# rev1_header_done.net
KiCad netlist of a schematic drawn in EAGLE
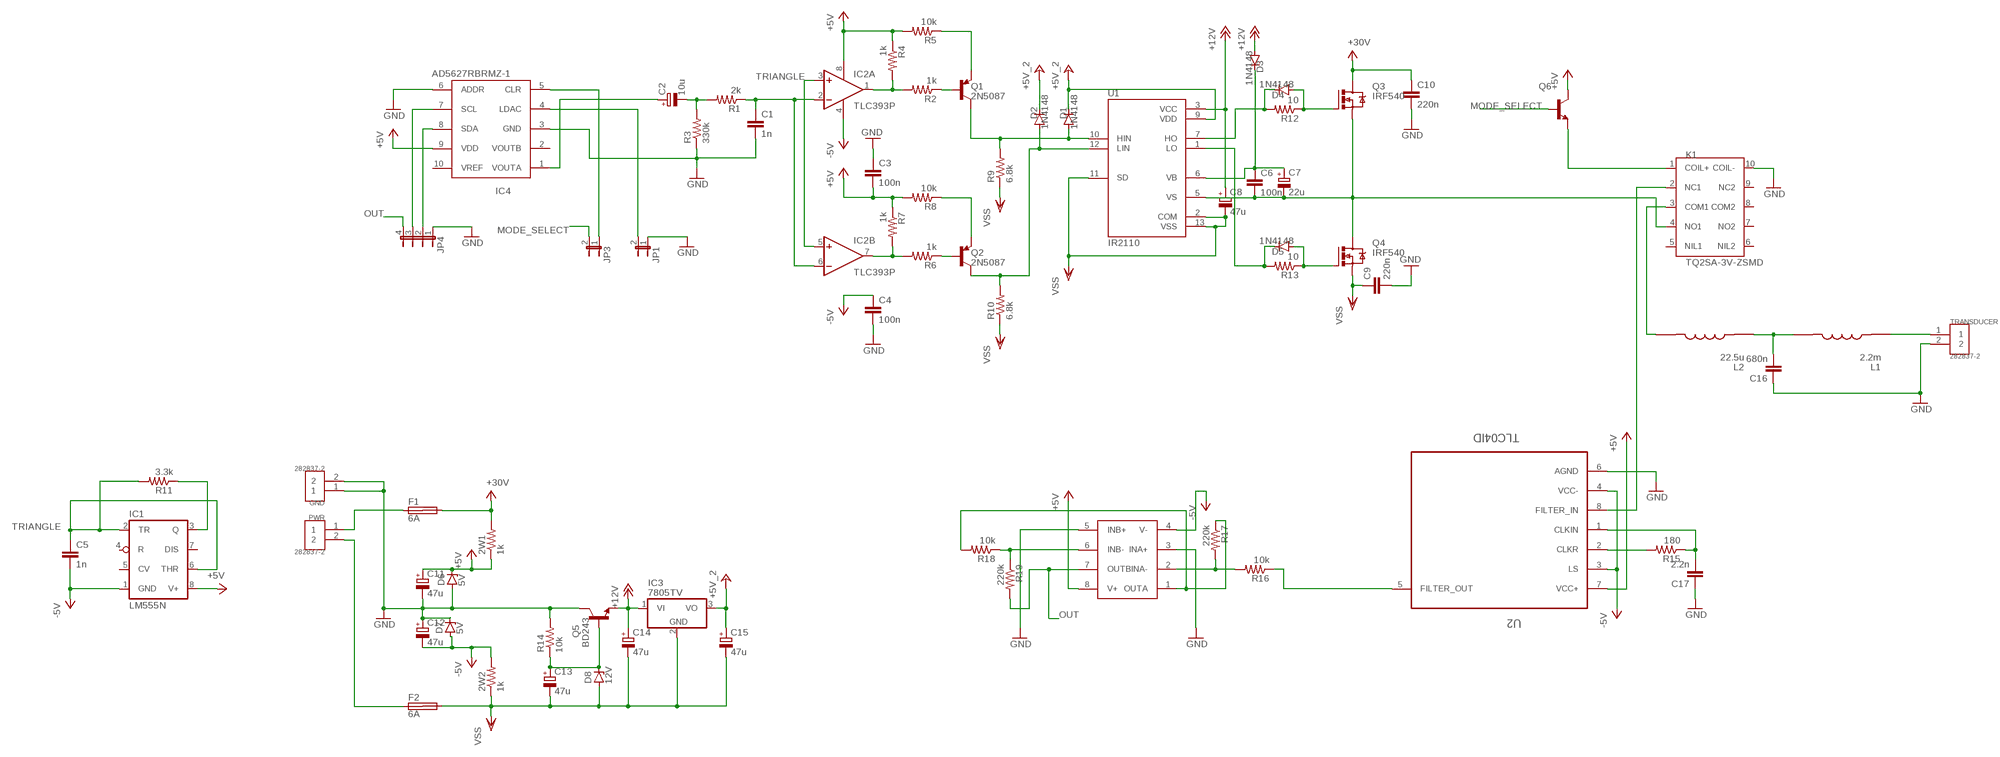
[diagram p0: schematic, sheet 1]

(export (version "E")
  (design (tool "Eeschema 10.0.6"))
  (components
    (comp (ref "2W1")
      (value "1k")
      (footprint "eagle-import:V235_17")
      (libsource (lib "eagle-import") (part "R-US_V235/17"))
    )
    (comp (ref "2W2")
      (value "1k")
      (footprint "eagle-import:V235_17")
      (libsource (lib "eagle-import") (part "R-US_V235/17"))
    )
    (comp (ref "C1")
      (value "1n")
      (footprint "eagle-import:C050-025X075")
      (libsource (lib "eagle-import") (part "C-EU050-025X075"))
    )
    (comp (ref "C2")
      (value "10u")
      (footprint "eagle-import:E2,5-6E")
      (libsource (lib "eagle-import") (part "CPOL-EUE2,5-6E"))
    )
    (comp (ref "C3")
      (value "100n")
      (footprint "eagle-import:C050-025X075")
      (libsource (lib "eagle-import") (part "C-EU050-025X075"))
    )
    (comp (ref "C4")
      (value "100n")
      (footprint "eagle-import:C050-025X075")
      (libsource (lib "eagle-import") (part "C-EU050-025X075"))
    )
    (comp (ref "C5")
      (value "1n")
      (footprint "eagle-import:C050-025X075")
      (libsource (lib "eagle-import") (part "C-EU050-025X075"))
    )
    (comp (ref "C6")
      (value "100n")
      (footprint "eagle-import:C050-025X075")
      (libsource (lib "eagle-import") (part "C-EU050-025X075"))
    )
    (comp (ref "C7")
      (value "22u")
      (footprint "eagle-import:E2,5-6E")
      (libsource (lib "eagle-import") (part "CPOL-EUE2,5-6E"))
    )
    (comp (ref "C8")
      (value "47u")
      (footprint "eagle-import:E2,5-6E")
      (libsource (lib "eagle-import") (part "CPOL-EUE2,5-6E"))
    )
    (comp (ref "C9")
      (value "220n")
      (footprint "eagle-import:C050-025X075")
      (libsource (lib "eagle-import") (part "C-EU050-025X075"))
    )
    (comp (ref "C10")
      (value "220n")
      (footprint "eagle-import:C050-025X075")
      (libsource (lib "eagle-import") (part "C-EU050-025X075"))
    )
    (comp (ref "C11")
      (value "47u")
      (footprint "eagle-import:E2,5-6E")
      (libsource (lib "eagle-import") (part "CPOL-EUE2,5-6E"))
    )
    (comp (ref "C12")
      (value "47u")
      (footprint "eagle-import:E2,5-6E")
      (libsource (lib "eagle-import") (part "CPOL-EUE2,5-6E"))
    )
    (comp (ref "C13")
      (value "47u")
      (footprint "eagle-import:E2,5-6E")
      (libsource (lib "eagle-import") (part "CPOL-EUE2,5-6E"))
    )
    (comp (ref "C14")
      (value "47u")
      (footprint "eagle-import:E2,5-6E")
      (libsource (lib "eagle-import") (part "CPOL-EUE2,5-6E"))
    )
    (comp (ref "C15")
      (value "47u")
      (footprint "eagle-import:E2,5-6E")
      (libsource (lib "eagle-import") (part "CPOL-EUE2,5-6E"))
    )
    (comp (ref "C16")
      (value "680n")
      (footprint "eagle-import:C050-025X075")
      (libsource (lib "eagle-import") (part "C-EU050-025X075"))
    )
    (comp (ref "C17")
      (value "2.2n")
      (footprint "eagle-import:C050-025X075")
      (libsource (lib "eagle-import") (part "C-EU050-025X075"))
    )
    (comp (ref "D1")
      (value "1N4148")
      (footprint "eagle-import:DO35-7")
      (libsource (lib "eagle-import") (part "1N4148DO35-7"))
    )
    (comp (ref "D2")
      (value "1N4148")
      (footprint "eagle-import:DO35-7")
      (libsource (lib "eagle-import") (part "1N4148DO35-7"))
    )
    (comp (ref "D3")
      (value "1N4148")
      (footprint "eagle-import:DO35-7")
      (libsource (lib "eagle-import") (part "1N4148DO35-7"))
    )
    (comp (ref "D4")
      (value "1N4148")
      (footprint "eagle-import:DO35-7")
      (libsource (lib "eagle-import") (part "1N4148DO35-7"))
    )
    (comp (ref "D5")
      (value "1N4148")
      (footprint "eagle-import:DO35-7")
      (libsource (lib "eagle-import") (part "1N4148DO35-7"))
    )
    (comp (ref "D6")
      (value "5V")
      (footprint "eagle-import:DO41Z10")
      (libsource (lib "eagle-import") (part "1N4728"))
    )
    (comp (ref "D7")
      (value "5V")
      (footprint "eagle-import:DO41Z10")
      (libsource (lib "eagle-import") (part "1N4728"))
    )
    (comp (ref "D8")
      (value "12V")
      (footprint "eagle-import:DO41Z10")
      (libsource (lib "eagle-import") (part "1N4728"))
    )
    (comp (ref "F1")
      (value "6A")
      (footprint "eagle-import:SHK20L")
      (libsource (lib "eagle-import") (part "SHK20L"))
    )
    (comp (ref "F2")
      (value "6A")
      (footprint "eagle-import:SHK20L")
      (libsource (lib "eagle-import") (part "SHK20L"))
    )
    (comp (ref "GND")
      (value "282837-2")
      (footprint "eagle-import:TE_282837-2")
      (fields (field (name "MF") "TE Connectivity"))
      (libsource (lib "eagle-import") (part "282837-2"))
    )
    (comp (ref "IC1")
      (value "LM555N")
      (footprint "eagle-import:DIL08")
      (libsource (lib "eagle-import") (part "555NLM"))
    )
    (comp (ref "IC2")
      (value "TLC393P")
      (footprint "eagle-import:DIL08")
      (libsource (lib "eagle-import") (part "TLC393P"))
    )
    (comp (ref "IC3")
      (value "7805TV")
      (footprint "eagle-import:TO220V")
      (libsource (lib "eagle-import") (part "78TV05"))
    )
    (comp (ref "IC4")
      (value "AD5627RBRMZ-1")
      (footprint "eagle-import:SOP50P490X110-10N")
      (libsource (lib "eagle-import") (part "AD5627RBRMZ-1"))
    )
    (comp (ref "IC5")
      (value "OP2177CRMZ")
      (footprint "eagle-import:SOP65P490X110-8N")
      (libsource (lib "eagle-import") (part "OP2177CRMZ"))
    )
    (comp (ref "JP1")
      (value "JP1E")
      (footprint "eagle-import:JP1")
      (libsource (lib "eagle-import") (part "JP1E"))
    )
    (comp (ref "JP3")
      (value "JP1E")
      (footprint "eagle-import:JP1")
      (libsource (lib "eagle-import") (part "JP1E"))
    )
    (comp (ref "JP4")
      (value "JP4E")
      (footprint "eagle-import:JP4")
      (libsource (lib "eagle-import") (part "JP4E"))
    )
    (comp (ref "K1")
      (value "TQ2SA-3V-ZSMD")
      (footprint "eagle-import:TQ2SA-3V-Z")
      (libsource (lib "eagle-import") (part "TQ2SA-3V-ZSMD"))
    )
    (comp (ref "L1")
      (value "2.2m")
      (footprint "eagle-import:IND_LQH43NN222K03L")
      (fields (field (name "MF") "Murata") (field (name "MP") "LQH43NN222K03L"))
      (libsource (lib "eagle-import") (part "LQH43NN222K03L"))
    )
    (comp (ref "L2")
      (value "22.5u")
      (footprint "eagle-import:IND_LQH43NN222K03L")
      (fields (field (name "MF") "Murata") (field (name "MP") "LQH43NN222K03L"))
      (libsource (lib "eagle-import") (part "LQH43NN222K03L"))
    )
    (comp (ref "PWR")
      (value "282837-2")
      (footprint "eagle-import:TE_282837-2")
      (fields (field (name "MF") "TE Connectivity"))
      (libsource (lib "eagle-import") (part "282837-2"))
    )
    (comp (ref "Q1")
      (value "2N5087")
      (footprint "eagle-import:TO92")
      (libsource (lib "eagle-import") (part "2N5087"))
    )
    (comp (ref "Q2")
      (value "2N5087")
      (footprint "eagle-import:TO92")
      (libsource (lib "eagle-import") (part "2N5087"))
    )
    (comp (ref "Q3")
      (value "IRF540")
      (footprint "eagle-import:TO220BV")
      (libsource (lib "eagle-import") (part "IRF540"))
    )
    (comp (ref "Q4")
      (value "IRF540")
      (footprint "eagle-import:TO220BV")
      (libsource (lib "eagle-import") (part "IRF540"))
    )
    (comp (ref "Q5")
      (value "BD243")
      (footprint "eagle-import:TO220")
      (libsource (lib "eagle-import") (part "BD243"))
    )
    (comp (ref "Q6")
      (value "-NPN-TO92")
      (footprint "eagle-import:TO92")
      (libsource (lib "eagle-import") (part "-NPN-TO92"))
    )
    (comp (ref "R1")
      (value "2k")
      (footprint "eagle-import:V234_12")
      (libsource (lib "eagle-import") (part "R-US_V234/12"))
    )
    (comp (ref "R2")
      (value "1k")
      (footprint "eagle-import:V234_12")
      (libsource (lib "eagle-import") (part "R-US_V234/12"))
    )
    (comp (ref "R3")
      (value "330k")
      (footprint "eagle-import:V234_12")
      (libsource (lib "eagle-import") (part "R-US_V234/12"))
    )
    (comp (ref "R4")
      (value "1k")
      (footprint "eagle-import:V234_12")
      (libsource (lib "eagle-import") (part "R-US_V234/12"))
    )
    (comp (ref "R5")
      (value "10k")
      (footprint "eagle-import:V234_12")
      (libsource (lib "eagle-import") (part "R-US_V234/12"))
    )
    (comp (ref "R6")
      (value "1k")
      (footprint "eagle-import:V234_12")
      (libsource (lib "eagle-import") (part "R-US_V234/12"))
    )
    (comp (ref "R7")
      (value "1k")
      (footprint "eagle-import:V234_12")
      (libsource (lib "eagle-import") (part "R-US_V234/12"))
    )
    (comp (ref "R8")
      (value "10k")
      (footprint "eagle-import:V234_12")
      (libsource (lib "eagle-import") (part "R-US_V234/12"))
    )
    (comp (ref "R9")
      (value "6.8k")
      (footprint "eagle-import:V234_12")
      (libsource (lib "eagle-import") (part "R-US_V234/12"))
    )
    (comp (ref "R10")
      (value "6.8k")
      (footprint "eagle-import:V234_12")
      (libsource (lib "eagle-import") (part "R-US_V234/12"))
    )
    (comp (ref "R11")
      (value "3.3k")
      (footprint "eagle-import:V234_12")
      (libsource (lib "eagle-import") (part "R-US_V234/12"))
    )
    (comp (ref "R12")
      (value "10")
      (footprint "eagle-import:V234_12")
      (libsource (lib "eagle-import") (part "R-US_V234/12"))
    )
    (comp (ref "R13")
      (value "10")
      (footprint "eagle-import:V234_12")
      (libsource (lib "eagle-import") (part "R-US_V234/12"))
    )
    (comp (ref "R14")
      (value "10k")
      (footprint "eagle-import:V234_12")
      (libsource (lib "eagle-import") (part "R-US_V234/12"))
    )
    (comp (ref "R15")
      (value "180")
      (footprint "eagle-import:V234_12")
      (libsource (lib "eagle-import") (part "R-US_V234/12"))
    )
    (comp (ref "R16")
      (value "10k")
      (footprint "eagle-import:V234_12")
      (libsource (lib "eagle-import") (part "R-US_V234/12"))
    )
    (comp (ref "R17")
      (value "220k")
      (footprint "eagle-import:V234_12")
      (libsource (lib "eagle-import") (part "R-US_V234/12"))
    )
    (comp (ref "R18")
      (value "10k")
      (footprint "eagle-import:V234_12")
      (libsource (lib "eagle-import") (part "R-US_V234/12"))
    )
    (comp (ref "R19")
      (value "220k")
      (footprint "eagle-import:V234_12")
      (libsource (lib "eagle-import") (part "R-US_V234/12"))
    )
    (comp (ref "TRANSDUCER")
      (value "282837-2")
      (footprint "eagle-import:TE_282837-2")
      (fields (field (name "MF") "TE Connectivity"))
      (libsource (lib "eagle-import") (part "282837-2"))
    )
    (comp (ref "U1")
      (value "IR2110")
      (footprint "eagle-import:DIP762W45P254L2019H533Q14")
      (fields (field (name "MF") "Infineon"))
      (libsource (lib "eagle-import") (part "IR2110"))
    )
    (comp (ref "U2")
      (value "TLC04ID")
      (footprint "eagle-import:SOIC127P600X175-8N")
      (fields (field (name "MF") "Texas Instruments"))
      (libsource (lib "eagle-import") (part "TLC04ID"))
    )
  )
  (nets
    (net (code "1") (name "+5V") (class "Default")
      (node (ref "2W1") (pin "1") (pinfunction "1_1") (pintype "passive"))
      (node (ref "C11") (pin "+") (pinfunction "+_+") (pintype "passive"))
      (node (ref "C3") (pin "2") (pinfunction "2_2") (pintype "passive"))
      (node (ref "D6") (pin "C") (pinfunction "C_C") (pintype "passive"))
      (node (ref "IC1") (pin "8") (pinfunction "V+_8") (pintype "power_in"))
      (node (ref "IC2") (pin "8") (pinfunction "V+_8") (pintype "power_in"))
      (node (ref "IC4") (pin "9") (pinfunction "VDD_9") (pintype "power_in"))
      (node (ref "IC5") (pin "8") (pinfunction "V+_8") (pintype "bidirectional"))
      (node (ref "Q6") (pin "3") (pinfunction "C_3") (pintype "passive"))
      (node (ref "R4") (pin "1") (pinfunction "1_1") (pintype "passive"))
      (node (ref "R5") (pin "2") (pinfunction "2_2") (pintype "passive"))
      (node (ref "R7") (pin "1") (pinfunction "1_1") (pintype "passive"))
      (node (ref "R8") (pin "2") (pinfunction "2_2") (pintype "passive"))
      (node (ref "U2") (pin "7") (pinfunction "VCC+_7") (pintype "power_in"))
    )
    (net (code "2") (name "+5V_2") (class "Default")
      (node (ref "C15") (pin "+") (pinfunction "+_+") (pintype "passive"))
      (node (ref "D1") (pin "C") (pinfunction "C_C") (pintype "passive"))
      (node (ref "D2") (pin "C") (pinfunction "C_C") (pintype "passive"))
      (node (ref "IC3") (pin "3") (pinfunction "VO_3") (pintype "passive"))
      (node (ref "U1") (pin "9") (pinfunction "VDD_9") (pintype "power_in"))
    )
    (net (code "3") (name "+12V") (class "Default")
      (node (ref "C14") (pin "+") (pinfunction "+_+") (pintype "passive"))
      (node (ref "C8") (pin "+") (pinfunction "+_+") (pintype "passive"))
      (node (ref "D3") (pin "A") (pinfunction "A_A") (pintype "passive"))
      (node (ref "IC3") (pin "1") (pinfunction "VI_1") (pintype "input"))
      (node (ref "Q5") (pin "3") (pinfunction "E_3") (pintype "passive"))
      (node (ref "U1") (pin "3") (pinfunction "VCC_3") (pintype "power_in"))
    )
    (net (code "4") (name "+30V") (class "Default")
      (node (ref "2W1") (pin "2") (pinfunction "2_2") (pintype "passive"))
      (node (ref "C10") (pin "1") (pinfunction "1_1") (pintype "passive"))
      (node (ref "F1") (pin "2A") (pinfunction "2A_2A") (pintype "passive"))
      (node (ref "Q3") (pin "D") (pinfunction "D_D") (pintype "passive"))
    )
    (net (code "5") (name "-5V") (class "Default")
      (node (ref "2W2") (pin "2") (pinfunction "2_2") (pintype "passive"))
      (node (ref "C12") (pin "-") (pinfunction "-_-") (pintype "passive"))
      (node (ref "C4") (pin "1") (pinfunction "1_1") (pintype "passive"))
      (node (ref "C5") (pin "2") (pinfunction "2_2") (pintype "passive"))
      (node (ref "D7") (pin "A") (pinfunction "A_A") (pintype "passive"))
      (node (ref "IC1") (pin "1") (pinfunction "GND_1") (pintype "power_in"))
      (node (ref "IC2") (pin "4") (pinfunction "V-_4") (pintype "power_in"))
      (node (ref "IC5") (pin "4") (pinfunction "V-_4") (pintype "bidirectional"))
      (node (ref "U2") (pin "3") (pinfunction "LS_3") (pintype "input"))
      (node (ref "U2") (pin "4") (pinfunction "VCC-_4") (pintype "power_in"))
    )
    (net (code "6") (name "/MODE_SELECT") (class "Default")
      (node (ref "JP3") (pin "2") (pinfunction "2_2") (pintype "passive"))
      (node (ref "Q6") (pin "2") (pinfunction "B_2") (pintype "passive"))
    )
    (net (code "7") (name "/OUT") (class "Default")
      (node (ref "IC5") (pin "7") (pinfunction "OUTB_7") (pintype "bidirectional"))
      (node (ref "JP4") (pin "4") (pinfunction "4_4") (pintype "passive"))
      (node (ref "R19") (pin "2") (pinfunction "2_2") (pintype "passive"))
    )
    (net (code "8") (name "/TRIANGLE") (class "Default")
      (node (ref "C5") (pin "1") (pinfunction "1_1") (pintype "passive"))
      (node (ref "IC1") (pin "2") (pinfunction "TR_2") (pintype "input"))
      (node (ref "IC1") (pin "6") (pinfunction "THR_6") (pintype "input"))
      (node (ref "IC2") (pin "3") (pinfunction "+IN_3") (pintype "input"))
      (node (ref "IC2") (pin "5") (pinfunction "+IN_5") (pintype "input"))
      (node (ref "R11") (pin "2") (pinfunction "2_2") (pintype "passive"))
    )
    (net (code "9") (name "GND") (class "Default")
      (node (ref "C1") (pin "2") (pinfunction "2_2") (pintype "passive"))
      (node (ref "C10") (pin "2") (pinfunction "2_2") (pintype "passive"))
      (node (ref "C11") (pin "-") (pinfunction "-_-") (pintype "passive"))
      (node (ref "C12") (pin "+") (pinfunction "+_+") (pintype "passive"))
      (node (ref "C16") (pin "1") (pinfunction "1_1") (pintype "passive"))
      (node (ref "C17") (pin "1") (pinfunction "1_1") (pintype "passive"))
      (node (ref "C3") (pin "1") (pinfunction "1_1") (pintype "passive"))
      (node (ref "C4") (pin "2") (pinfunction "2_2") (pintype "passive"))
      (node (ref "C9") (pin "2") (pinfunction "2_2") (pintype "passive"))
      (node (ref "D6") (pin "A") (pinfunction "A_A") (pintype "passive"))
      (node (ref "D7") (pin "C") (pinfunction "C_C") (pintype "passive"))
      (node (ref "GND") (pin "1") (pinfunction "1_1") (pintype "passive"))
      (node (ref "GND") (pin "2") (pinfunction "2_2") (pintype "passive"))
      (node (ref "IC4") (pin "3") (pinfunction "GND_3") (pintype "power_in"))
      (node (ref "IC4") (pin "6") (pinfunction "ADDR_6") (pintype "bidirectional"))
      (node (ref "IC5") (pin "3") (pinfunction "INA+_3") (pintype "bidirectional"))
      (node (ref "IC5") (pin "5") (pinfunction "INB+_5") (pintype "bidirectional"))
      (node (ref "JP1") (pin "1") (pinfunction "1_1") (pintype "passive"))
      (node (ref "JP4") (pin "1") (pinfunction "1_1") (pintype "passive"))
      (node (ref "K1") (pin "10") (pinfunction "COIL-_10") (pintype "bidirectional"))
      (node (ref "Q5") (pin "2") (pinfunction "C_2") (pintype "passive"))
      (node (ref "R14") (pin "2") (pinfunction "2_2") (pintype "passive"))
      (node (ref "R3") (pin "1") (pinfunction "1_1") (pintype "passive"))
      (node (ref "TRANSDUCER") (pin "2") (pinfunction "2_2") (pintype "passive"))
      (node (ref "U2") (pin "6") (pinfunction "AGND_6") (pintype "passive"))
    )
    (net (code "10") (name "Net-(C2-Pad-)") (class "Default")
      (node (ref "C2") (pin "-") (pinfunction "-_-") (pintype "passive"))
      (node (ref "R1") (pin "2") (pinfunction "2_2") (pintype "passive"))
      (node (ref "R3") (pin "2") (pinfunction "2_2") (pintype "passive"))
    )
    (net (code "11") (name "Net-(C16-Pad2)") (class "Default")
      (node (ref "C16") (pin "2") (pinfunction "2_2") (pintype "passive"))
      (node (ref "L1") (pin "2") (pinfunction "2_2") (pintype "passive"))
      (node (ref "L2") (pin "1") (pinfunction "1_1") (pintype "passive"))
    )
    (net (code "12") (name "Net-(D4-PadA)") (class "Default")
      (node (ref "D4") (pin "A") (pinfunction "A_A") (pintype "passive"))
      (node (ref "Q3") (pin "G") (pinfunction "G_G") (pintype "passive"))
      (node (ref "R12") (pin "1") (pinfunction "1_1") (pintype "passive"))
    )
    (net (code "13") (name "Net-(D5-PadA)") (class "Default")
      (node (ref "D5") (pin "A") (pinfunction "A_A") (pintype "passive"))
      (node (ref "Q4") (pin "G") (pinfunction "G_G") (pintype "passive"))
      (node (ref "R13") (pin "1") (pinfunction "1_1") (pintype "passive"))
    )
    (net (code "14") (name "Net-(F1-Pad1A)") (class "Default")
      (node (ref "F1") (pin "1A") (pinfunction "1A_1A") (pintype "passive"))
      (node (ref "PWR") (pin "1") (pinfunction "1_1") (pintype "passive"))
    )
    (net (code "15") (name "Net-(F2-Pad1A)") (class "Default")
      (node (ref "F2") (pin "1A") (pinfunction "1A_1A") (pintype "passive"))
      (node (ref "PWR") (pin "2") (pinfunction "2_2") (pintype "passive"))
    )
    (net (code "16") (name "Net-(IC1-Q)") (class "Default")
      (node (ref "IC1") (pin "3") (pinfunction "Q_3") (pintype "output"))
      (node (ref "R11") (pin "1") (pinfunction "1_1") (pintype "passive"))
    )
    (net (code "17") (name "Net-(IC2A--IN)") (class "Default")
      (node (ref "C1") (pin "1") (pinfunction "1_1") (pintype "passive"))
      (node (ref "IC2") (pin "2") (pinfunction "-IN_2") (pintype "input"))
      (node (ref "IC2") (pin "6") (pinfunction "-IN_6") (pintype "input"))
      (node (ref "R1") (pin "1") (pinfunction "1_1") (pintype "passive"))
    )
    (net (code "18") (name "Net-(IC2A-OUT)") (class "Default")
      (node (ref "IC2") (pin "1") (pinfunction "OUT_1") (pintype "output"))
      (node (ref "R2") (pin "2") (pinfunction "2_2") (pintype "passive"))
      (node (ref "R4") (pin "2") (pinfunction "2_2") (pintype "passive"))
    )
    (net (code "19") (name "Net-(IC2B-OUT)") (class "Default")
      (node (ref "IC2") (pin "7") (pinfunction "OUT_7") (pintype "output"))
      (node (ref "R6") (pin "2") (pinfunction "2_2") (pintype "passive"))
      (node (ref "R7") (pin "2") (pinfunction "2_2") (pintype "passive"))
    )
    (net (code "20") (name "Net-(IC4-CLR)") (class "Default")
      (node (ref "IC4") (pin "5") (pinfunction "CLR_5") (pintype "bidirectional"))
      (node (ref "JP3") (pin "1") (pinfunction "1_1") (pintype "passive"))
    )
    (net (code "21") (name "Net-(IC4-LDAC)") (class "Default")
      (node (ref "IC4") (pin "4") (pinfunction "LDAC_4") (pintype "bidirectional"))
      (node (ref "JP1") (pin "2") (pinfunction "2_2") (pintype "passive"))
    )
    (net (code "22") (name "Net-(IC4-SCL)") (class "Default")
      (node (ref "IC4") (pin "7") (pinfunction "SCL_7") (pintype "bidirectional"))
      (node (ref "JP4") (pin "3") (pinfunction "3_3") (pintype "passive"))
    )
    (net (code "23") (name "Net-(IC4-SDA)") (class "Default")
      (node (ref "IC4") (pin "8") (pinfunction "SDA_8") (pintype "bidirectional"))
      (node (ref "JP4") (pin "2") (pinfunction "2_2") (pintype "passive"))
    )
    (net (code "24") (name "Net-(IC4-VOUTA)") (class "Default")
      (node (ref "C2") (pin "+") (pinfunction "+_+") (pintype "passive"))
      (node (ref "IC4") (pin "1") (pinfunction "VOUTA_1") (pintype "bidirectional"))
    )
    (net (code "25") (name "Net-(IC5-INA-)") (class "Default")
      (node (ref "IC5") (pin "2") (pinfunction "INA-_2") (pintype "bidirectional"))
      (node (ref "R16") (pin "2") (pinfunction "2_2") (pintype "passive"))
      (node (ref "R17") (pin "2") (pinfunction "2_2") (pintype "passive"))
    )
    (net (code "26") (name "Net-(IC5-INB-)") (class "Default")
      (node (ref "IC5") (pin "6") (pinfunction "INB-_6") (pintype "bidirectional"))
      (node (ref "R18") (pin "1") (pinfunction "1_1") (pintype "passive"))
      (node (ref "R19") (pin "1") (pinfunction "1_1") (pintype "passive"))
    )
    (net (code "27") (name "Net-(IC5-OUTA)") (class "Default")
      (node (ref "IC5") (pin "1") (pinfunction "OUTA_1") (pintype "bidirectional"))
      (node (ref "R17") (pin "1") (pinfunction "1_1") (pintype "passive"))
      (node (ref "R18") (pin "2") (pinfunction "2_2") (pintype "passive"))
    )
    (net (code "28") (name "Net-(K1-COIL+)") (class "Default")
      (node (ref "K1") (pin "1") (pinfunction "COIL+_1") (pintype "bidirectional"))
      (node (ref "Q6") (pin "1") (pinfunction "E_1") (pintype "passive"))
    )
    (net (code "29") (name "Net-(K1-COM1)") (class "Default")
      (node (ref "K1") (pin "3") (pinfunction "COM1_3") (pintype "bidirectional"))
      (node (ref "L2") (pin "2") (pinfunction "2_2") (pintype "passive"))
    )
    (net (code "30") (name "Net-(K1-NC1)") (class "Default")
      (node (ref "K1") (pin "2") (pinfunction "NC1_2") (pintype "bidirectional"))
      (node (ref "U2") (pin "8") (pinfunction "FILTER_IN_8") (pintype "input"))
    )
    (net (code "31") (name "Net-(K1-NO1)") (class "Default")
      (node (ref "C6") (pin "2") (pinfunction "2_2") (pintype "passive"))
      (node (ref "C7") (pin "-") (pinfunction "-_-") (pintype "passive"))
      (node (ref "K1") (pin "4") (pinfunction "NO1_4") (pintype "bidirectional"))
      (node (ref "Q3") (pin "S") (pinfunction "S_S") (pintype "passive"))
      (node (ref "Q4") (pin "D") (pinfunction "D_D") (pintype "passive"))
      (node (ref "U1") (pin "5") (pinfunction "VS_5") (pintype "passive"))
    )
    (net (code "32") (name "Net-(L1-Pad1)") (class "Default")
      (node (ref "L1") (pin "1") (pinfunction "1_1") (pintype "passive"))
      (node (ref "TRANSDUCER") (pin "1") (pinfunction "1_1") (pintype "passive"))
    )
    (net (code "33") (name "Net-(Q1-B)") (class "Default")
      (node (ref "Q1") (pin "2") (pinfunction "B_2") (pintype "passive"))
      (node (ref "R2") (pin "1") (pinfunction "1_1") (pintype "passive"))
    )
    (net (code "34") (name "Net-(Q1-C)") (class "Default")
      (node (ref "D1") (pin "A") (pinfunction "A_A") (pintype "passive"))
      (node (ref "Q1") (pin "1") (pinfunction "C_1") (pintype "passive"))
      (node (ref "R9") (pin "2") (pinfunction "2_2") (pintype "passive"))
      (node (ref "U1") (pin "10") (pinfunction "HIN_10") (pintype "input"))
    )
    (net (code "35") (name "Net-(Q1-E)") (class "Default")
      (node (ref "Q1") (pin "3") (pinfunction "E_3") (pintype "passive"))
      (node (ref "R5") (pin "1") (pinfunction "1_1") (pintype "passive"))
    )
    (net (code "36") (name "Net-(Q2-B)") (class "Default")
      (node (ref "Q2") (pin "2") (pinfunction "B_2") (pintype "passive"))
      (node (ref "R6") (pin "1") (pinfunction "1_1") (pintype "passive"))
    )
    (net (code "37") (name "Net-(Q2-C)") (class "Default")
      (node (ref "D2") (pin "A") (pinfunction "A_A") (pintype "passive"))
      (node (ref "Q2") (pin "1") (pinfunction "C_1") (pintype "passive"))
      (node (ref "R10") (pin "2") (pinfunction "2_2") (pintype "passive"))
      (node (ref "U1") (pin "12") (pinfunction "LIN_12") (pintype "input"))
    )
    (net (code "38") (name "Net-(Q2-E)") (class "Default")
      (node (ref "Q2") (pin "3") (pinfunction "E_3") (pintype "passive"))
      (node (ref "R8") (pin "1") (pinfunction "1_1") (pintype "passive"))
    )
    (net (code "39") (name "Net-(Q5-B)") (class "Default")
      (node (ref "C13") (pin "+") (pinfunction "+_+") (pintype "passive"))
      (node (ref "D8") (pin "C") (pinfunction "C_C") (pintype "passive"))
      (node (ref "Q5") (pin "1") (pinfunction "B_1") (pintype "passive"))
      (node (ref "R14") (pin "1") (pinfunction "1_1") (pintype "passive"))
    )
    (net (code "40") (name "Net-(U1-HO)") (class "Default")
      (node (ref "D4") (pin "C") (pinfunction "C_C") (pintype "passive"))
      (node (ref "R12") (pin "2") (pinfunction "2_2") (pintype "passive"))
      (node (ref "U1") (pin "7") (pinfunction "HO_7") (pintype "output"))
    )
    (net (code "41") (name "Net-(U1-LO)") (class "Default")
      (node (ref "D5") (pin "C") (pinfunction "C_C") (pintype "passive"))
      (node (ref "R13") (pin "2") (pinfunction "2_2") (pintype "passive"))
      (node (ref "U1") (pin "1") (pinfunction "LO_1") (pintype "output"))
    )
    (net (code "42") (name "Net-(U1-VB)") (class "Default")
      (node (ref "C6") (pin "1") (pinfunction "1_1") (pintype "passive"))
      (node (ref "C7") (pin "+") (pinfunction "+_+") (pintype "passive"))
      (node (ref "D3") (pin "C") (pinfunction "C_C") (pintype "passive"))
      (node (ref "U1") (pin "6") (pinfunction "VB_6") (pintype "passive"))
    )
    (net (code "43") (name "Net-(U2-CLKIN)") (class "Default")
      (node (ref "C17") (pin "2") (pinfunction "2_2") (pintype "passive"))
      (node (ref "R15") (pin "1") (pinfunction "1_1") (pintype "passive"))
      (node (ref "U2") (pin "1") (pinfunction "CLKIN_1") (pintype "input"))
    )
    (net (code "44") (name "Net-(U2-CLKR)") (class "Default")
      (node (ref "R15") (pin "2") (pinfunction "2_2") (pintype "passive"))
      (node (ref "U2") (pin "2") (pinfunction "CLKR_2") (pintype "input"))
    )
    (net (code "45") (name "Net-(U2-FILTER_OUT)") (class "Default")
      (node (ref "R16") (pin "1") (pinfunction "1_1") (pintype "passive"))
      (node (ref "U2") (pin "5") (pinfunction "FILTER_OUT_5") (pintype "output"))
    )
    (net (code "46") (name "VSS") (class "Default")
      (node (ref "2W2") (pin "1") (pinfunction "1_1") (pintype "passive"))
      (node (ref "C13") (pin "-") (pinfunction "-_-") (pintype "passive"))
      (node (ref "C14") (pin "-") (pinfunction "-_-") (pintype "passive"))
      (node (ref "C15") (pin "-") (pinfunction "-_-") (pintype "passive"))
      (node (ref "C8") (pin "-") (pinfunction "-_-") (pintype "passive"))
      (node (ref "C9") (pin "1") (pinfunction "1_1") (pintype "passive"))
      (node (ref "D8") (pin "A") (pinfunction "A_A") (pintype "passive"))
      (node (ref "F2") (pin "2A") (pinfunction "2A_2A") (pintype "passive"))
      (node (ref "IC3") (pin "2") (pinfunction "GND_2") (pintype "passive"))
      (node (ref "Q4") (pin "S") (pinfunction "S_S") (pintype "passive"))
      (node (ref "R10") (pin "1") (pinfunction "1_1") (pintype "passive"))
      (node (ref "R9") (pin "1") (pinfunction "1_1") (pintype "passive"))
      (node (ref "U1") (pin "11") (pinfunction "SD_11") (pintype "input"))
      (node (ref "U1") (pin "13") (pinfunction "VSS_13") (pintype "power_in"))
      (node (ref "U1") (pin "2") (pinfunction "COM_2") (pintype "power_in"))
    )
    (net (code "47") (name "unconnected-(F1-Pad1B)") (class "Default")
      (node (ref "F1") (pin "1B") (pinfunction "1B_1B") (pintype "passive"))
    )
    (net (code "48") (name "unconnected-(F1-Pad2B)") (class "Default")
      (node (ref "F1") (pin "2B") (pinfunction "2B_2B") (pintype "passive"))
    )
    (net (code "49") (name "unconnected-(F2-Pad1B)") (class "Default")
      (node (ref "F2") (pin "1B") (pinfunction "1B_1B") (pintype "passive"))
    )
    (net (code "50") (name "unconnected-(F2-Pad2B)") (class "Default")
      (node (ref "F2") (pin "2B") (pinfunction "2B_2B") (pintype "passive"))
    )
    (net (code "51") (name "unconnected-(IC1-CV-Pad5)") (class "Default")
      (node (ref "IC1") (pin "5") (pinfunction "CV_5") (pintype "input"))
    )
    (net (code "52") (name "unconnected-(IC1-DIS-Pad7)") (class "Default")
      (node (ref "IC1") (pin "7") (pinfunction "DIS_7") (pintype "input"))
    )
    (net (code "53") (name "unconnected-(IC1-R-Pad4)") (class "Default")
      (node (ref "IC1") (pin "4") (pinfunction "R_4") (pintype "input"))
    )
    (net (code "54") (name "unconnected-(IC4-VOUTB-Pad2)") (class "Default")
      (node (ref "IC4") (pin "2") (pinfunction "VOUTB_2") (pintype "bidirectional"))
    )
    (net (code "55") (name "unconnected-(IC4-VREF-Pad10)") (class "Default")
      (node (ref "IC4") (pin "10") (pinfunction "VREF_10") (pintype "bidirectional"))
    )
    (net (code "56") (name "unconnected-(K1-COM2-Pad8)") (class "Default")
      (node (ref "K1") (pin "8") (pinfunction "COM2_8") (pintype "bidirectional"))
    )
    (net (code "57") (name "unconnected-(K1-NC2-Pad9)") (class "Default")
      (node (ref "K1") (pin "9") (pinfunction "NC2_9") (pintype "bidirectional"))
    )
    (net (code "58") (name "unconnected-(K1-NIL1-Pad5)") (class "Default")
      (node (ref "K1") (pin "5") (pinfunction "NIL1_5") (pintype "no_connect"))
    )
    (net (code "59") (name "unconnected-(K1-NIL2-Pad6)") (class "Default")
      (node (ref "K1") (pin "6") (pinfunction "NIL2_6") (pintype "no_connect"))
    )
    (net (code "60") (name "unconnected-(K1-NO2-Pad7)") (class "Default")
      (node (ref "K1") (pin "7") (pinfunction "NO2_7") (pintype "bidirectional"))
    )
  )
)
